# Dock_P1RA.net
KiCad netlist of a schematic drawn in EAGLE
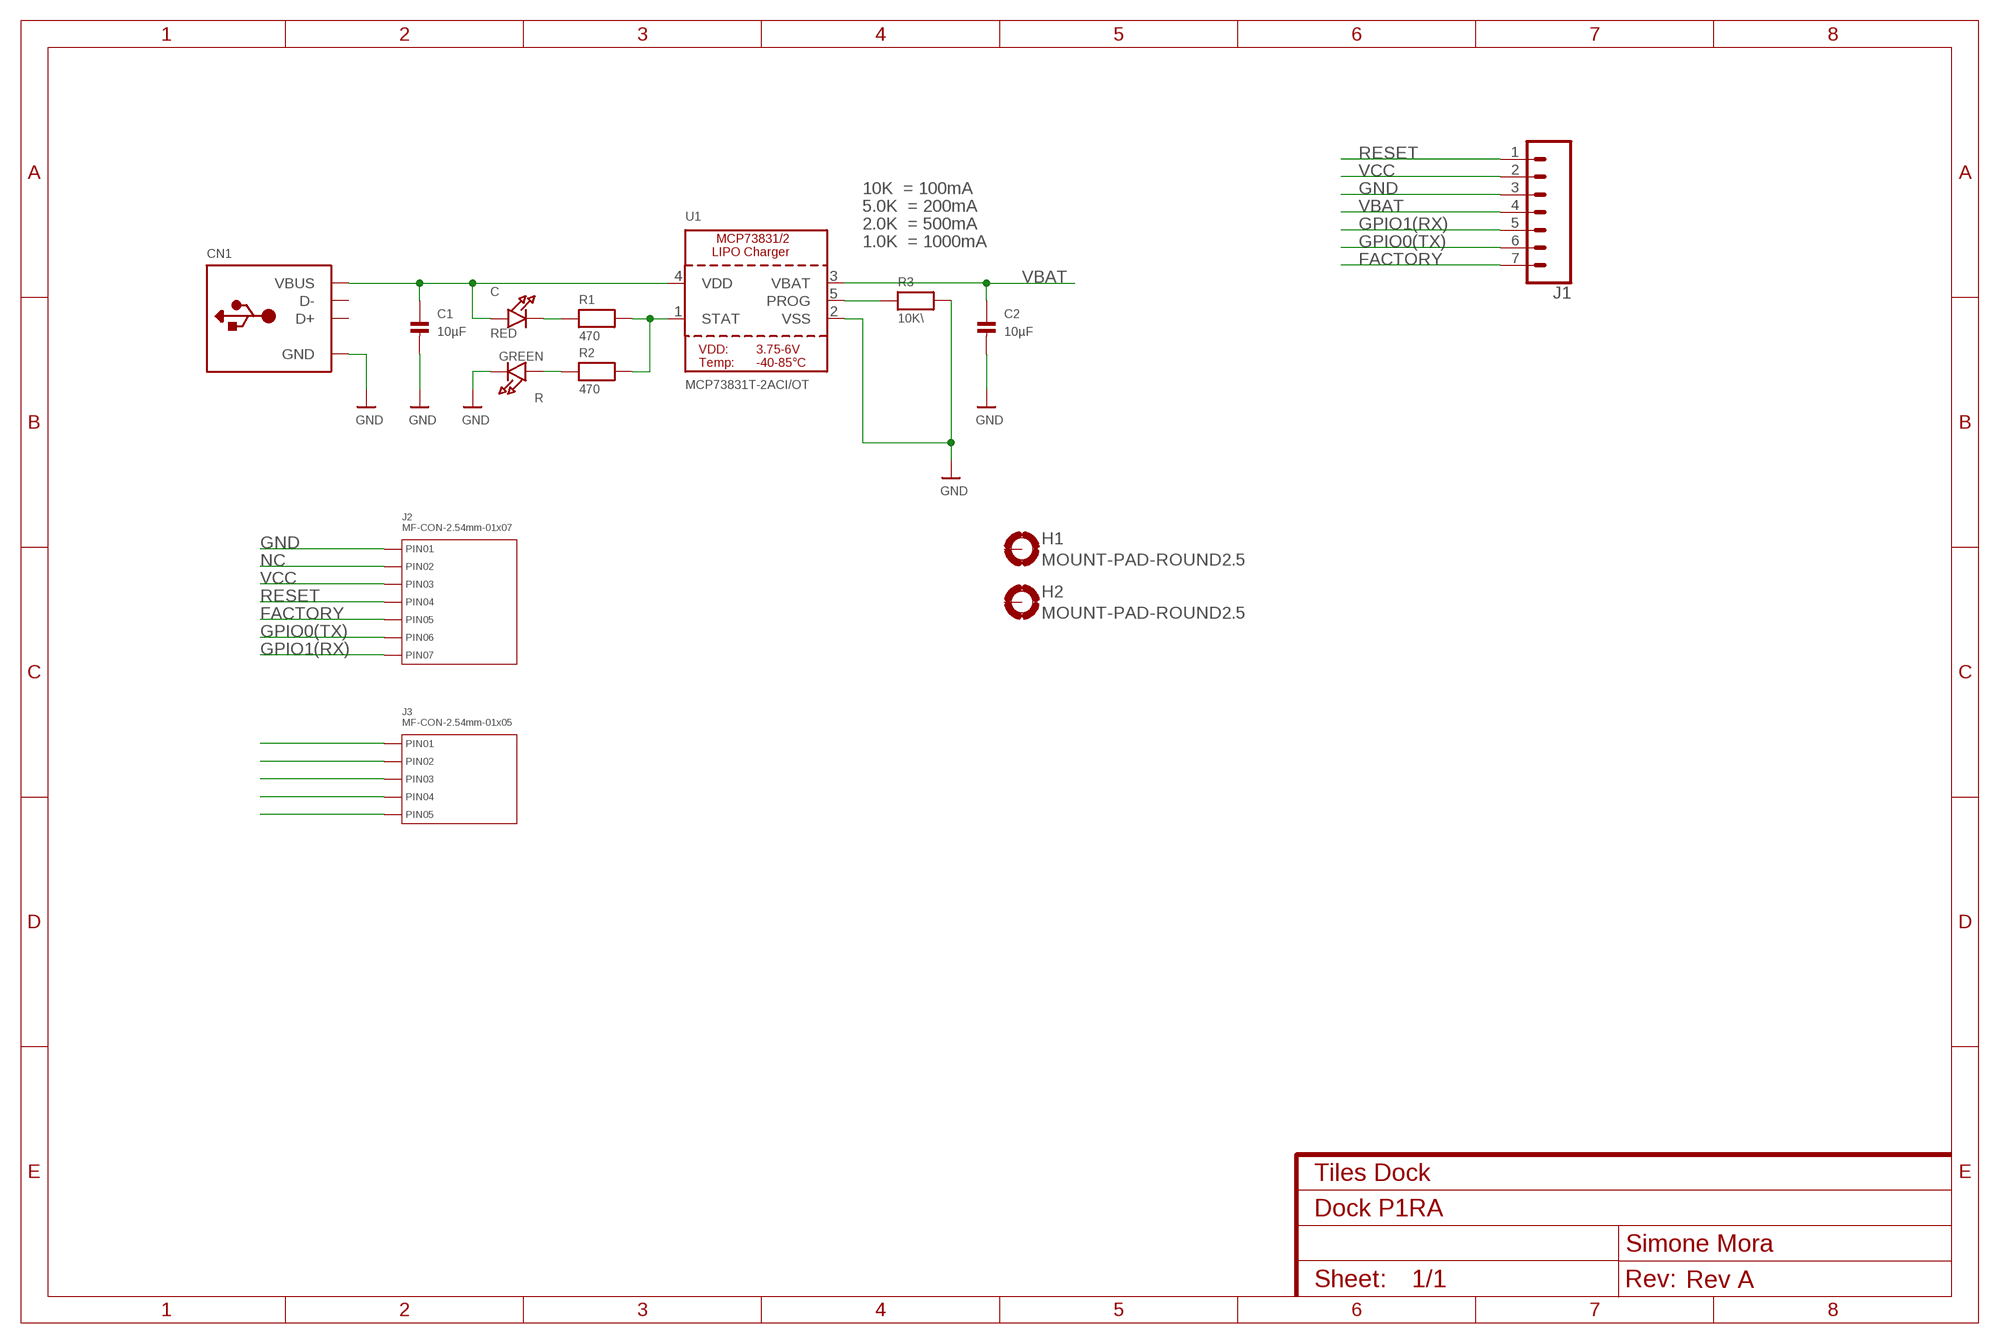
[diagram p0: schematic, sheet 1]

(export (version "E")
  (design (tool "Eeschema 10.0.6"))
  (components
    (comp (ref "C")
      (value "RED")
      (footprint "eagle-import:CHIPLED_0805")
      (libsource (lib "eagle-import") (part "LED0805"))
    )
    (comp (ref "C1")
      (value "10µF")
      (footprint "eagle-import:1206")
      (libsource (lib "eagle-import") (part "CAP_CERAMIC1206"))
    )
    (comp (ref "C2")
      (value "10µF")
      (footprint "eagle-import:1206")
      (libsource (lib "eagle-import") (part "CAP_CERAMIC1206"))
    )
    (comp (ref "CN1")
      (value "USB_TYPEAPCB")
      (footprint "eagle-import:USBA_PCB")
      (libsource (lib "eagle-import") (part "USB_TYPEAPCB"))
    )
    (comp (ref "H1")
      (value "MOUNT-PAD-ROUND2.5")
      (footprint "eagle-import:2,5-PAD-SIM")
      (libsource (lib "eagle-import") (part "MOUNT-PAD-ROUND2.5"))
    )
    (comp (ref "H2")
      (value "MOUNT-PAD-ROUND2.5")
      (footprint "eagle-import:2,5-PAD-SIM")
      (libsource (lib "eagle-import") (part "MOUNT-PAD-ROUND2.5"))
    )
    (comp (ref "J1")
      (value "CONN_07_SIMSQPAD_TOP")
      (footprint "eagle-import:1X07_SQUAREPADS_TOP")
      (libsource (lib "eagle-import") (part "CONN_07_SIMSQPAD_TOP"))
    )
    (comp (ref "J2")
      (value "MF-CON-2.54mm-01x07")
      (footprint "eagle-import:PTH_2.54MM_01X07")
      (fields (field (name "HOUSEPART") "YES"))
      (libsource (lib "eagle-import") (part "CON_01X07_PTH_2.54MM"))
    )
    (comp (ref "J3")
      (value "MF-CON-2.54mm-01x05")
      (footprint "eagle-import:PTH_2.54MM_01X05")
      (fields (field (name "HOUSEPART") "YES"))
      (libsource (lib "eagle-import") (part "CON_01X05_PTH_2.54MM"))
    )
    (comp (ref "R")
      (value "GREEN")
      (footprint "eagle-import:CHIPLED_0805")
      (libsource (lib "eagle-import") (part "LED0805"))
    )
    (comp (ref "R1")
      (value "470")
      (footprint "eagle-import:0805")
      (libsource (lib "eagle-import") (part "RESISTOR0805"))
    )
    (comp (ref "R2")
      (value "470")
      (footprint "eagle-import:0805")
      (libsource (lib "eagle-import") (part "RESISTOR0805"))
    )
    (comp (ref "R3")
      (value "10K\\")
      (footprint "eagle-import:0805")
      (libsource (lib "eagle-import") (part "RESISTOR0805"))
    )
    (comp (ref "U1")
      (value "MCP73831T-2ACI/OT")
      (footprint "eagle-import:SOT23-5")
      (libsource (lib "eagle-import") (part "MCP73831/2"))
    )
  )
  (nets
    (net (code "1") (name "/FACTORY") (class "Default")
      (node (ref "J1") (pin "7") (pinfunction "7_7") (pintype "passive"))
      (node (ref "J2") (pin "P$5") (pinfunction "PIN5_P$5") (pintype "bidirectional"))
    )
    (net (code "2") (name "/GPIO0(TX)") (class "Default")
      (node (ref "J1") (pin "6") (pinfunction "6_6") (pintype "passive"))
      (node (ref "J2") (pin "P$6") (pinfunction "PIN6_P$6") (pintype "bidirectional"))
    )
    (net (code "3") (name "/GPIO1(RX)") (class "Default")
      (node (ref "J1") (pin "5") (pinfunction "5_5") (pintype "passive"))
      (node (ref "J2") (pin "P$7") (pinfunction "PIN7_P$7") (pintype "bidirectional"))
    )
    (net (code "4") (name "/NC") (class "Default")
      (node (ref "J2") (pin "P$2") (pinfunction "PIN2_P$2") (pintype "bidirectional"))
    )
    (net (code "5") (name "/RESET") (class "Default")
      (node (ref "J1") (pin "1") (pinfunction "1_1") (pintype "passive"))
      (node (ref "J2") (pin "P$4") (pinfunction "PIN4_P$4") (pintype "bidirectional"))
    )
    (net (code "6") (name "/VBAT") (class "Default")
      (node (ref "C2") (pin "1") (pinfunction "P$1_1") (pintype "passive"))
      (node (ref "J1") (pin "4") (pinfunction "4_4") (pintype "passive"))
      (node (ref "U1") (pin "3") (pinfunction "VBAT_3") (pintype "power_in"))
    )
    (net (code "7") (name "/VCC") (class "Default")
      (node (ref "J1") (pin "2") (pinfunction "2_2") (pintype "passive"))
      (node (ref "J2") (pin "P$3") (pinfunction "PIN3_P$3") (pintype "bidirectional"))
    )
    (net (code "8") (name "GND") (class "Default")
      (node (ref "C1") (pin "2") (pinfunction "P$2_2") (pintype "passive"))
      (node (ref "C2") (pin "2") (pinfunction "P$2_2") (pintype "passive"))
      (node (ref "CN1") (pin "GND") (pinfunction "GND_GND") (pintype "power_in"))
      (node (ref "J1") (pin "3") (pinfunction "3_3") (pintype "passive"))
      (node (ref "J2") (pin "P$1") (pinfunction "PIN1_P$1") (pintype "bidirectional"))
      (node (ref "R") (pin "C") (pinfunction "C_C") (pintype "passive"))
      (node (ref "R3") (pin "2") (pinfunction "2_2") (pintype "passive"))
      (node (ref "U1") (pin "2") (pinfunction "VSS_2") (pintype "power_in"))
    )
    (net (code "9") (name "Net-(C-PadC)") (class "Default")
      (node (ref "C") (pin "C") (pinfunction "C_C") (pintype "passive"))
      (node (ref "R1") (pin "1") (pinfunction "1_1") (pintype "passive"))
    )
    (net (code "10") (name "Net-(C1-P$1)") (class "Default")
      (node (ref "C") (pin "A") (pinfunction "A_A") (pintype "passive"))
      (node (ref "C1") (pin "1") (pinfunction "P$1_1") (pintype "passive"))
      (node (ref "CN1") (pin "VCC") (pinfunction "VBUS_VCC") (pintype "power_in"))
      (node (ref "U1") (pin "4") (pinfunction "VDD_4") (pintype "power_in"))
    )
    (net (code "11") (name "Net-(R-PadA)") (class "Default")
      (node (ref "R") (pin "A") (pinfunction "A_A") (pintype "passive"))
      (node (ref "R2") (pin "1") (pinfunction "1_1") (pintype "passive"))
    )
    (net (code "12") (name "Net-(U1-PROG)") (class "Default")
      (node (ref "R3") (pin "1") (pinfunction "1_1") (pintype "passive"))
      (node (ref "U1") (pin "5") (pinfunction "PROG_5") (pintype "input"))
    )
    (net (code "13") (name "Net-(U1-STAT)") (class "Default")
      (node (ref "R1") (pin "2") (pinfunction "2_2") (pintype "passive"))
      (node (ref "R2") (pin "2") (pinfunction "2_2") (pintype "passive"))
      (node (ref "U1") (pin "1") (pinfunction "STAT_1") (pintype "output"))
    )
    (net (code "14") (name "unconnected-(CN1-D+-PadUSB_PLUS)") (class "Default")
      (node (ref "CN1") (pin "USB_PLUS") (pinfunction "D+_USB_PLUS") (pintype "bidirectional"))
    )
    (net (code "15") (name "unconnected-(CN1-D--PadUSB_NEG)") (class "Default")
      (node (ref "CN1") (pin "USB_NEG") (pinfunction "D-_USB_NEG") (pintype "bidirectional"))
    )
    (net (code "16") (name "unconnected-(H1-MOUNT-PadB2,8)") (class "Default")
      (node (ref "H1") (pin "B2,8") (pinfunction "MOUNT_B2,8") (pintype "passive"))
    )
    (net (code "17") (name "unconnected-(H2-MOUNT-PadB2,8)") (class "Default")
      (node (ref "H2") (pin "B2,8") (pinfunction "MOUNT_B2,8") (pintype "passive"))
    )
    (net (code "18") (name "unconnected-(J3-PIN1-PadP$1)") (class "Default")
      (node (ref "J3") (pin "P$1") (pinfunction "PIN1_P$1") (pintype "bidirectional"))
    )
    (net (code "19") (name "unconnected-(J3-PIN2-PadP$2)") (class "Default")
      (node (ref "J3") (pin "P$2") (pinfunction "PIN2_P$2") (pintype "bidirectional"))
    )
    (net (code "20") (name "unconnected-(J3-PIN3-PadP$3)") (class "Default")
      (node (ref "J3") (pin "P$3") (pinfunction "PIN3_P$3") (pintype "bidirectional"))
    )
    (net (code "21") (name "unconnected-(J3-PIN4-PadP$4)") (class "Default")
      (node (ref "J3") (pin "P$4") (pinfunction "PIN4_P$4") (pintype "bidirectional"))
    )
    (net (code "22") (name "unconnected-(J3-PIN5-PadP$5)") (class "Default")
      (node (ref "J3") (pin "P$5") (pinfunction "PIN5_P$5") (pintype "bidirectional"))
    )
  )
)
